# Preamp_Filter.net
KiCad netlist of a schematic drawn in Altium Designer
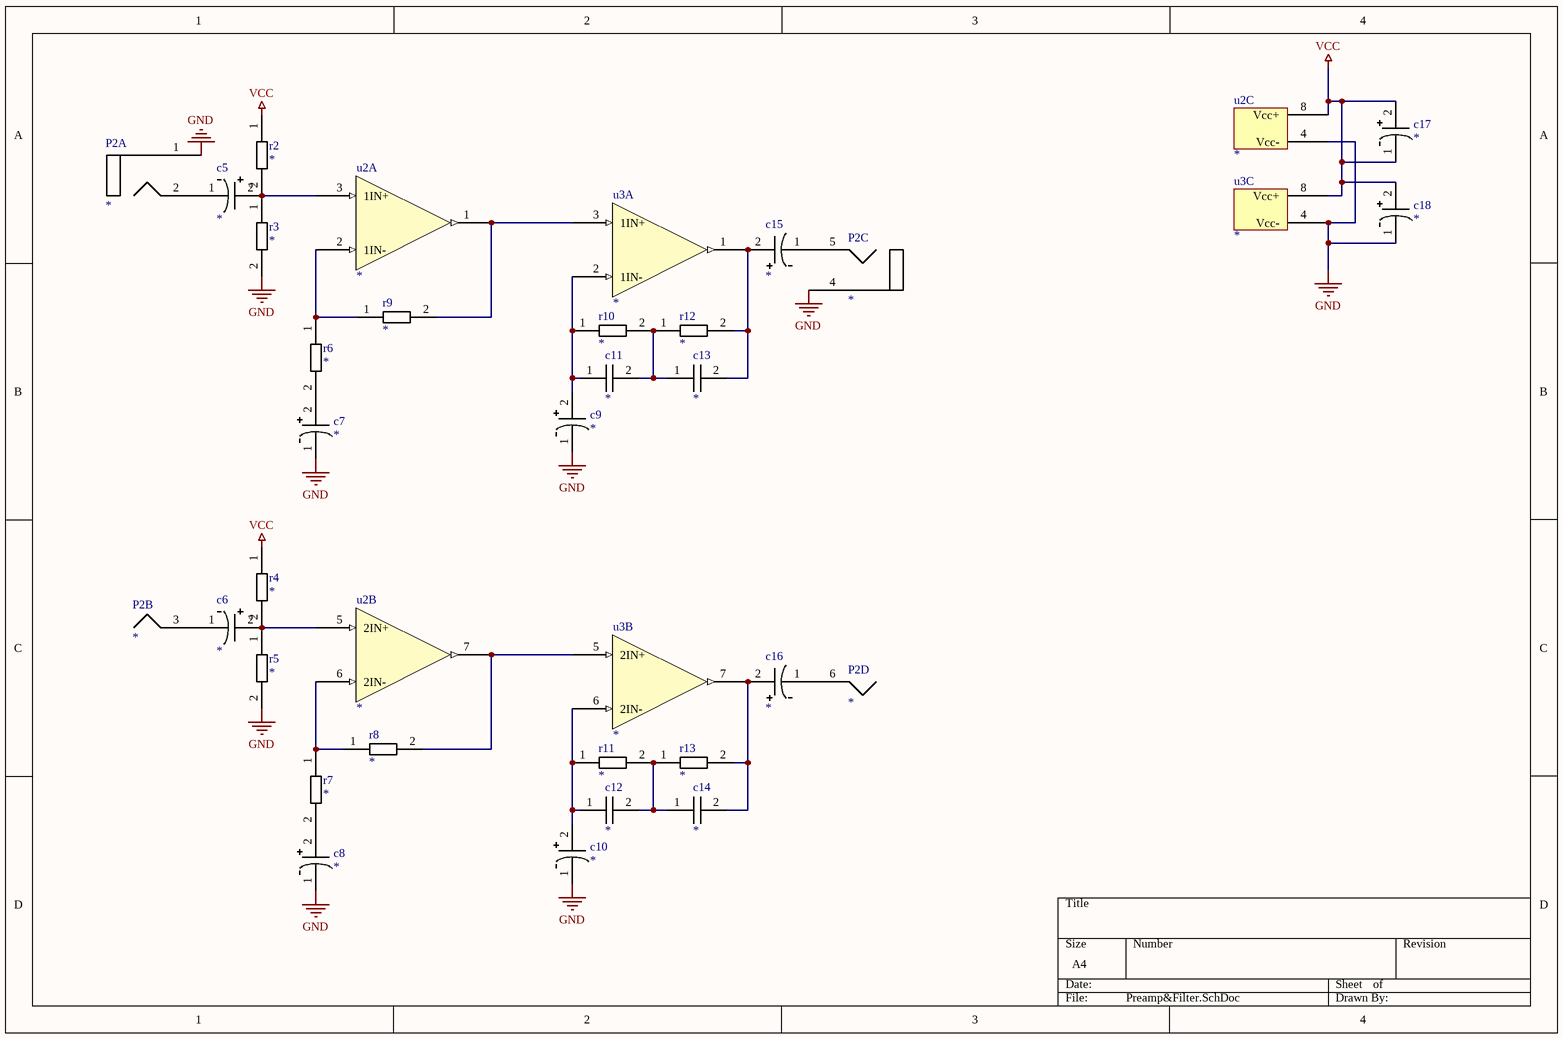
[diagram p0: Preamp&Filter.SchDoc]

(export (version "E")
  (design (tool "Eeschema 10.0.6"))
  (components
    (comp (ref "c5") (value "*") (footprint "Elco-B") (libsource (lib "") (part "Elco B_1")))
    (comp (ref "c6") (value "*") (footprint "Elco-B") (libsource (lib "") (part "Elco B_1")))
    (comp (ref "c7") (value "*") (footprint "Elco-B") (libsource (lib "Panasonic") (part "Elco B")))
    (comp (ref "c8") (value "*") (footprint "Elco-B") (libsource (lib "Panasonic") (part "Elco B")))
    (comp (ref "c9")
      (value "*")
      (footprint "Elco-D")
      (description "Elco size D 6.3x5.4")
      (libsource (lib "Panasonic") (part "Elco D"))
    )
    (comp (ref "c10")
      (value "*")
      (footprint "Elco-D")
      (description "Elco size D 6.3x5.4")
      (libsource (lib "Panasonic") (part "Elco D"))
    )
    (comp (ref "c11")
      (value "*")
      (footprint "0805")
      (description "0805 Capacitor Package")
      (libsource (lib "Generic R-C") (part "0805 Capacitor"))
    )
    (comp (ref "c12")
      (value "*")
      (footprint "0805")
      (description "0805 Capacitor Package")
      (libsource (lib "Generic R-C") (part "0805 Capacitor"))
    )
    (comp (ref "c13")
      (value "*")
      (footprint "0805")
      (description "0805 Capacitor Package")
      (libsource (lib "Generic R-C") (part "0805 Capacitor"))
    )
    (comp (ref "c14")
      (value "*")
      (footprint "0805")
      (description "0805 Capacitor Package")
      (libsource (lib "Generic R-C") (part "0805 Capacitor"))
    )
    (comp (ref "c15") (value "*") (footprint "Elco-C") (libsource (lib "Panasonic") (part "Elco C")))
    (comp (ref "c16") (value "*") (footprint "Elco-C") (libsource (lib "Panasonic") (part "Elco C")))
    (comp (ref "c17")
      (value "*")
      (footprint "Elco-D")
      (description "Elco size D 6.3x5.4")
      (libsource (lib "Panasonic") (part "Elco D"))
    )
    (comp (ref "c18")
      (value "*")
      (footprint "Elco-D")
      (description "Elco size D 6.3x5.4")
      (libsource (lib "Panasonic") (part "Elco D"))
    )
    (comp (ref "P2")
      (value "*")
      (footprint "RCA 4-way")
      (description "4-way RCA connector")
      (libsource (lib "Pro-Signal") (part "PSG01551"))
    )
    (comp (ref "r2")
      (value "*")
      (footprint "0805")
      (description "0805 Resistor package")
      (libsource (lib "Generic R-C") (part "0805 Resistor"))
    )
    (comp (ref "r3")
      (value "*")
      (footprint "0805")
      (description "0805 Resistor package")
      (libsource (lib "Generic R-C") (part "0805 Resistor"))
    )
    (comp (ref "r4")
      (value "*")
      (footprint "0805")
      (description "0805 Resistor package")
      (libsource (lib "Generic R-C") (part "0805 Resistor"))
    )
    (comp (ref "r5")
      (value "*")
      (footprint "0805")
      (description "0805 Resistor package")
      (libsource (lib "Generic R-C") (part "0805 Resistor"))
    )
    (comp (ref "r6")
      (value "*")
      (footprint "0805")
      (description "0805 Resistor package")
      (libsource (lib "Generic R-C") (part "0805 Resistor"))
    )
    (comp (ref "r7")
      (value "*")
      (footprint "0805")
      (description "0805 Resistor package")
      (libsource (lib "Generic R-C") (part "0805 Resistor"))
    )
    (comp (ref "r8")
      (value "*")
      (footprint "0805")
      (description "0805 Resistor package")
      (libsource (lib "Generic R-C") (part "0805 Resistor"))
    )
    (comp (ref "r9")
      (value "*")
      (footprint "0805")
      (description "0805 Resistor package")
      (libsource (lib "Generic R-C") (part "0805 Resistor"))
    )
    (comp (ref "r10")
      (value "*")
      (footprint "0805")
      (description "0805 Resistor package")
      (libsource (lib "Generic R-C") (part "0805 Resistor"))
    )
    (comp (ref "r11")
      (value "*")
      (footprint "0805")
      (description "0805 Resistor package")
      (libsource (lib "Generic R-C") (part "0805 Resistor"))
    )
    (comp (ref "r12")
      (value "*")
      (footprint "0805")
      (description "0805 Resistor package")
      (libsource (lib "Generic R-C") (part "0805 Resistor"))
    )
    (comp (ref "r13")
      (value "*")
      (footprint "0805")
      (description "0805 Resistor package")
      (libsource (lib "Generic R-C") (part "0805 Resistor"))
    )
    (comp (ref "u2")
      (value "*")
      (footprint "R-PDSO-G8-P127d620x530")
      (description "Dual Low-Noise OpAmp")
      (libsource (lib "Texas Instruments") (part "NE5532x"))
    )
    (comp (ref "u3")
      (value "*")
      (footprint "R-PDSO-G8-P127d620x530")
      (description "Low-Noise JFET-input OpAmp")
      (libsource (lib "Texas Instruments") (part "TL027x"))
    )
  )
  (nets
    (net (code "1") (name "GND") (class "Default")
      (node (ref "P2") (pin "1") (pintype "power_in"))
      (node (ref "P2") (pin "4") (pintype "power_in"))
      (node (ref "c10") (pin "1") (pintype "passive"))
      (node (ref "c18") (pin "1") (pintype "passive"))
      (node (ref "c7") (pin "1") (pintype "passive"))
      (node (ref "c8") (pin "1") (pintype "passive"))
      (node (ref "c9") (pin "1") (pintype "passive"))
      (node (ref "r3") (pin "2") (pintype "passive"))
      (node (ref "r5") (pin "2") (pintype "passive"))
      (node (ref "u2") (pin "4") (pinfunction "Vcc-_4") (pintype "power_in"))
      (node (ref "u3") (pin "4") (pinfunction "Vcc-_4") (pintype "power_in"))
    )
    (net (code "2") (name "Net-(P2-Pad2)") (class "Default")
      (node (ref "P2") (pin "2") (pintype "passive"))
      (node (ref "c5") (pin "1") (pintype "passive"))
    )
    (net (code "3") (name "Net-(P2-Pad3)") (class "Default")
      (node (ref "P2") (pin "3") (pintype "passive"))
      (node (ref "c6") (pin "1") (pintype "passive"))
    )
    (net (code "4") (name "Net-(P2-Pad5)") (class "Default")
      (node (ref "P2") (pin "5") (pintype "passive"))
      (node (ref "c15") (pin "1") (pintype "passive"))
    )
    (net (code "5") (name "Net-(P2-Pad6)") (class "Default")
      (node (ref "P2") (pin "6") (pintype "passive"))
      (node (ref "c16") (pin "1") (pintype "passive"))
    )
    (net (code "6") (name "Net-(c7-Pad2)") (class "Default")
      (node (ref "c7") (pin "2") (pintype "passive"))
      (node (ref "r6") (pin "2") (pintype "passive"))
    )
    (net (code "7") (name "Net-(c8-Pad2)") (class "Default")
      (node (ref "c8") (pin "2") (pintype "passive"))
      (node (ref "r7") (pin "2") (pintype "passive"))
    )
    (net (code "8") (name "Net-(c11-Pad2)") (class "Default")
      (node (ref "c11") (pin "2") (pintype "passive"))
      (node (ref "c13") (pin "1") (pintype "passive"))
      (node (ref "r10") (pin "2") (pintype "passive"))
      (node (ref "r12") (pin "1") (pintype "passive"))
    )
    (net (code "9") (name "Net-(c12-Pad2)") (class "Default")
      (node (ref "c12") (pin "2") (pintype "passive"))
      (node (ref "c14") (pin "1") (pintype "passive"))
      (node (ref "r11") (pin "2") (pintype "passive"))
      (node (ref "r13") (pin "1") (pintype "passive"))
    )
    (net (code "10") (name "Net-(u2A-1IN+)") (class "Default")
      (node (ref "c5") (pin "2") (pintype "passive"))
      (node (ref "r2") (pin "2") (pintype "passive"))
      (node (ref "r3") (pin "1") (pintype "passive"))
      (node (ref "u2") (pin "3") (pinfunction "1IN+_3") (pintype "input"))
    )
    (net (code "11") (name "Net-(u2A-1IN-)") (class "Default")
      (node (ref "r6") (pin "1") (pintype "passive"))
      (node (ref "r9") (pin "1") (pintype "passive"))
      (node (ref "u2") (pin "2") (pinfunction "1IN-_2") (pintype "input"))
    )
    (net (code "12") (name "Net-(u2A-1OUT)") (class "Default")
      (node (ref "r9") (pin "2") (pintype "passive"))
      (node (ref "u2") (pin "1") (pinfunction "1OUT_1") (pintype "output"))
      (node (ref "u3") (pin "3") (pinfunction "1IN+_3") (pintype "input"))
    )
    (net (code "13") (name "Net-(u2B-2IN+)") (class "Default")
      (node (ref "c6") (pin "2") (pintype "passive"))
      (node (ref "r4") (pin "2") (pintype "passive"))
      (node (ref "r5") (pin "1") (pintype "passive"))
      (node (ref "u2") (pin "5") (pinfunction "2IN+_5") (pintype "input"))
    )
    (net (code "14") (name "Net-(u2B-2IN-)") (class "Default")
      (node (ref "r7") (pin "1") (pintype "passive"))
      (node (ref "r8") (pin "1") (pintype "passive"))
      (node (ref "u2") (pin "6") (pinfunction "2IN-_6") (pintype "input"))
    )
    (net (code "15") (name "Net-(u2B-2OUT)") (class "Default")
      (node (ref "r8") (pin "2") (pintype "passive"))
      (node (ref "u2") (pin "7") (pinfunction "2OUT_7") (pintype "output"))
      (node (ref "u3") (pin "5") (pinfunction "2IN+_5") (pintype "input"))
    )
    (net (code "16") (name "Net-(u3A-1IN-)") (class "Default")
      (node (ref "c11") (pin "1") (pintype "passive"))
      (node (ref "c9") (pin "2") (pintype "passive"))
      (node (ref "r10") (pin "1") (pintype "passive"))
      (node (ref "u3") (pin "2") (pinfunction "1IN-_2") (pintype "input"))
    )
    (net (code "17") (name "Net-(u3A-1OUT)") (class "Default")
      (node (ref "c13") (pin "2") (pintype "passive"))
      (node (ref "c15") (pin "2") (pintype "passive"))
      (node (ref "r12") (pin "2") (pintype "passive"))
      (node (ref "u3") (pin "1") (pinfunction "1OUT_1") (pintype "output"))
    )
    (net (code "18") (name "Net-(u3B-2IN-)") (class "Default")
      (node (ref "c10") (pin "2") (pintype "passive"))
      (node (ref "c12") (pin "1") (pintype "passive"))
      (node (ref "r11") (pin "1") (pintype "passive"))
      (node (ref "u3") (pin "6") (pinfunction "2IN-_6") (pintype "input"))
    )
    (net (code "19") (name "Net-(u3B-2OUT)") (class "Default")
      (node (ref "c14") (pin "2") (pintype "passive"))
      (node (ref "c16") (pin "2") (pintype "passive"))
      (node (ref "r13") (pin "2") (pintype "passive"))
      (node (ref "u3") (pin "7") (pinfunction "2OUT_7") (pintype "output"))
    )
    (net (code "20") (name "VCC") (class "Default")
      (node (ref "c17") (pin "1") (pintype "passive"))
      (node (ref "c17") (pin "2") (pintype "passive"))
      (node (ref "c18") (pin "2") (pintype "passive"))
      (node (ref "r2") (pin "1") (pintype "passive"))
      (node (ref "r4") (pin "1") (pintype "passive"))
      (node (ref "u2") (pin "8") (pinfunction "Vcc+_8") (pintype "power_in"))
      (node (ref "u3") (pin "8") (pinfunction "Vcc+_8") (pintype "power_in"))
    )
  )
)
